# TUSB8041-Q1-4port_Hub.net
KiCad netlist of a schematic drawn in Altium Designer
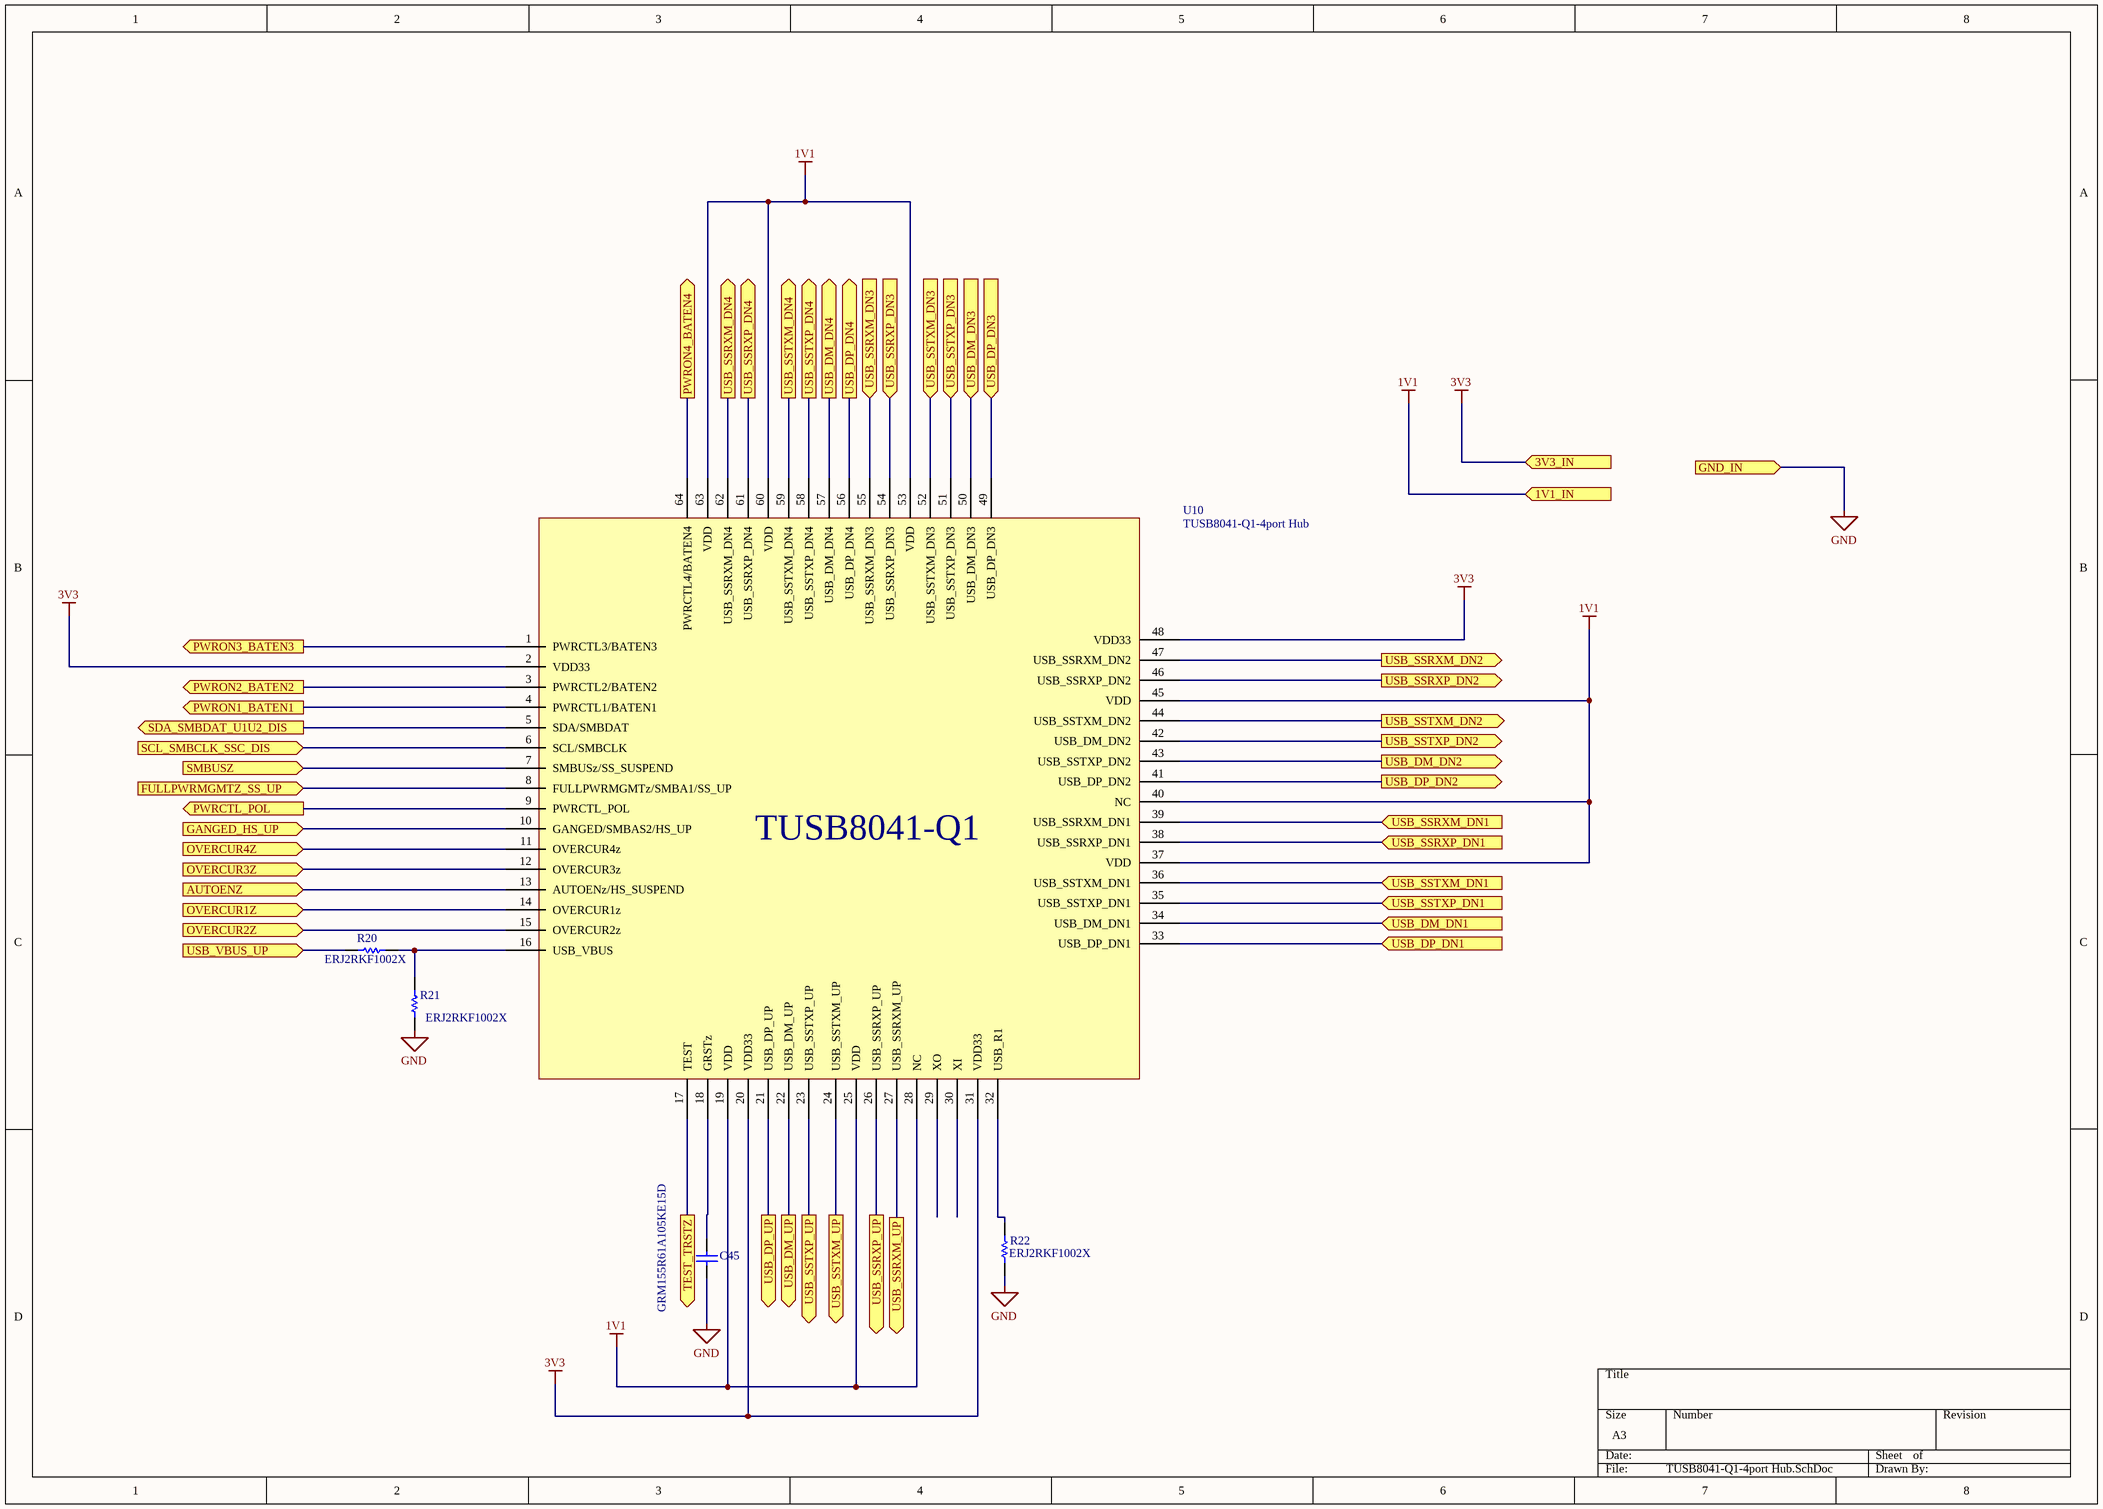
[diagram p0: TUSB8041-Q1-4port Hub.SchDoc]

(export (version "E")
  (design (tool "Eeschema 10.0.6"))
  (components
    (comp (ref "C45")
      (value "GRM155R61A105KE15D")
      (footprint "CAPC1005X55X25NL05T10")
      (fields (field (name "MANUFACTURER") "Murata"))
      (libsource (lib "Altium Content Vault") (part "CAP"))
    )
    (comp (ref "R20")
      (value "ERJ2RKF1002X")
      (footprint "RESC1005X40X25LL05T05")
      (description "Chip Resistor, 10 KOhm, +/- 1%, 0.1 W, -55 to 155 degC, 0402 (1005 Metric), RoHS, Tape and Reel")
      (fields (field (name "TOLERANCE") "1%") (field (name "MANUFACTURER") "Panasonic"))
      (libsource (lib "Altium Content Vault") (part "RES-2"))
    )
    (comp (ref "R21")
      (value "ERJ2RKF1002X")
      (footprint "RESC1005X40X25LL05T05")
      (description "Chip Resistor, 10 KOhm, +/- 1%, 0.1 W, -55 to 155 degC, 0402 (1005 Metric), RoHS, Tape and Reel")
      (fields (field (name "TOLERANCE") "1%") (field (name "MANUFACTURER") "Panasonic"))
      (libsource (lib "Altium Content Vault") (part "RES-2"))
    )
    (comp (ref "R22")
      (value "ERJ2RKF1002X")
      (footprint "RESC1005X40X25LL05T05")
      (description "Chip Resistor, 10 KOhm, +/- 1%, 0.1 W, -55 to 155 degC, 0402 (1005 Metric), RoHS, Tape and Reel")
      (fields (field (name "TOLERANCE") "1%") (field (name "MANUFACTURER") "Panasonic"))
      (libsource (lib "Altium Content Vault") (part "RES-2"))
    )
    (comp (ref "U10")
      (value "TUSB8041-Q1-4port Hub")
      (footprint "TSQFP50P1200X1200X120-64N")
      (libsource (lib "PlumPot_Library") (part "TUSB8041-Q1-4port Hub"))
    )
  )
  (nets
    (net (code "1") (name "/AUTOENZ") (class "Default")
      (node (ref "U10") (pin "13") (pinfunction "AUTOENz/HS_SUSPEND_13") (pintype "passive"))
    )
    (net (code "2") (name "/FULLPWRMGMTZ_SS_UP") (class "Default")
      (node (ref "U10") (pin "8") (pinfunction "FULLPWRMGMTz/SMBA1/SS_UP_8") (pintype "passive"))
    )
    (net (code "3") (name "/GANGED_HS_UP") (class "Default")
      (node (ref "U10") (pin "10") (pinfunction "GANGED/SMBAS2/HS_UP_10") (pintype "passive"))
    )
    (net (code "4") (name "/OVERCUR1Z") (class "Default")
      (node (ref "U10") (pin "14") (pinfunction "OVERCUR1z_14") (pintype "passive"))
    )
    (net (code "5") (name "/OVERCUR2Z") (class "Default")
      (node (ref "U10") (pin "15") (pinfunction "OVERCUR2z_15") (pintype "passive"))
    )
    (net (code "6") (name "/OVERCUR3Z") (class "Default")
      (node (ref "U10") (pin "12") (pinfunction "OVERCUR3z_12") (pintype "passive"))
    )
    (net (code "7") (name "/OVERCUR4Z") (class "Default")
      (node (ref "U10") (pin "11") (pinfunction "OVERCUR4z_11") (pintype "passive"))
    )
    (net (code "8") (name "/PWRCTL_POL") (class "Default")
      (node (ref "U10") (pin "9") (pinfunction "PWRCTL_POL_9") (pintype "passive"))
    )
    (net (code "9") (name "/PWRON1_BATEN1") (class "Default")
      (node (ref "U10") (pin "4") (pinfunction "PWRCTL1/BATEN1_4") (pintype "passive"))
    )
    (net (code "10") (name "/PWRON2_BATEN2") (class "Default")
      (node (ref "U10") (pin "3") (pinfunction "PWRCTL2/BATEN2_3") (pintype "passive"))
    )
    (net (code "11") (name "/PWRON3_BATEN3") (class "Default")
      (node (ref "U10") (pin "1") (pinfunction "PWRCTL3/BATEN3_1") (pintype "passive"))
    )
    (net (code "12") (name "/PWRON4_BATEN4") (class "Default")
      (node (ref "U10") (pin "64") (pinfunction "PWRCTL4/BATEN4_64") (pintype "passive"))
    )
    (net (code "13") (name "/SCL_SMBCLK_SSC_DIS") (class "Default")
      (node (ref "U10") (pin "6") (pinfunction "SCL/SMBCLK_6") (pintype "passive"))
    )
    (net (code "14") (name "/SDA_SMBDAT_U1U2_DIS") (class "Default")
      (node (ref "U10") (pin "5") (pinfunction "SDA/SMBDAT_5") (pintype "passive"))
    )
    (net (code "15") (name "/SMBUSZ") (class "Default")
      (node (ref "U10") (pin "7") (pinfunction "SMBUSz/SS_SUSPEND_7") (pintype "passive"))
    )
    (net (code "16") (name "/TEST_TRSTZ") (class "Default")
      (node (ref "U10") (pin "17") (pinfunction "TEST_17") (pintype "passive"))
    )
    (net (code "17") (name "/USB_DM_DN1") (class "Default")
      (node (ref "U10") (pin "34") (pinfunction "USB_DM_DN1_34") (pintype "passive"))
    )
    (net (code "18") (name "/USB_DM_DN2") (class "Default")
      (node (ref "U10") (pin "43") (pinfunction "USB_SSTXP_DN2_43") (pintype "passive"))
    )
    (net (code "19") (name "/USB_DM_DN3") (class "Default")
      (node (ref "U10") (pin "50") (pinfunction "USB_DM_DN3_50") (pintype "passive"))
    )
    (net (code "20") (name "/USB_DM_DN4") (class "Default")
      (node (ref "U10") (pin "57") (pinfunction "USB_DM_DN4_57") (pintype "passive"))
    )
    (net (code "21") (name "/USB_DM_UP") (class "Default")
      (node (ref "U10") (pin "22") (pinfunction "USB_DM_UP_22") (pintype "passive"))
    )
    (net (code "22") (name "/USB_DP_DN1") (class "Default")
      (node (ref "U10") (pin "33") (pinfunction "USB_DP_DN1_33") (pintype "passive"))
    )
    (net (code "23") (name "/USB_DP_DN2") (class "Default")
      (node (ref "U10") (pin "41") (pinfunction "USB_DP_DN2_41") (pintype "passive"))
    )
    (net (code "24") (name "/USB_DP_DN3") (class "Default")
      (node (ref "U10") (pin "49") (pinfunction "USB_DP_DN3_49") (pintype "passive"))
    )
    (net (code "25") (name "/USB_DP_DN4") (class "Default")
      (node (ref "U10") (pin "56") (pinfunction "USB_DP_DN4_56") (pintype "passive"))
    )
    (net (code "26") (name "/USB_DP_UP") (class "Default")
      (node (ref "U10") (pin "21") (pinfunction "USB_DP_UP_21") (pintype "passive"))
    )
    (net (code "27") (name "/USB_SSRXM_DN1") (class "Default")
      (node (ref "U10") (pin "39") (pinfunction "USB_SSRXM_DN1_39") (pintype "passive"))
    )
    (net (code "28") (name "/USB_SSRXM_DN2") (class "Default")
      (node (ref "U10") (pin "47") (pinfunction "USB_SSRXM_DN2_47") (pintype "passive"))
    )
    (net (code "29") (name "/USB_SSRXM_DN3") (class "Default")
      (node (ref "U10") (pin "55") (pinfunction "USB_SSRXM_DN3_55") (pintype "passive"))
    )
    (net (code "30") (name "/USB_SSRXM_DN4") (class "Default")
      (node (ref "U10") (pin "62") (pinfunction "USB_SSRXM_DN4_62") (pintype "passive"))
    )
    (net (code "31") (name "/USB_SSRXM_UP") (class "Default")
      (node (ref "U10") (pin "27") (pinfunction "USB_SSRXM_UP_27") (pintype "passive"))
    )
    (net (code "32") (name "/USB_SSRXP_DN1") (class "Default")
      (node (ref "U10") (pin "38") (pinfunction "USB_SSRXP_DN1_38") (pintype "passive"))
    )
    (net (code "33") (name "/USB_SSRXP_DN2") (class "Default")
      (node (ref "U10") (pin "46") (pinfunction "USB_SSRXP_DN2_46") (pintype "passive"))
    )
    (net (code "34") (name "/USB_SSRXP_DN3") (class "Default")
      (node (ref "U10") (pin "54") (pinfunction "USB_SSRXP_DN3_54") (pintype "passive"))
    )
    (net (code "35") (name "/USB_SSRXP_DN4") (class "Default")
      (node (ref "U10") (pin "61") (pinfunction "USB_SSRXP_DN4_61") (pintype "passive"))
    )
    (net (code "36") (name "/USB_SSRXP_UP") (class "Default")
      (node (ref "U10") (pin "26") (pinfunction "USB_SSRXP_UP_26") (pintype "passive"))
    )
    (net (code "37") (name "/USB_SSTXM_DN1") (class "Default")
      (node (ref "U10") (pin "36") (pinfunction "USB_SSTXM_DN1_36") (pintype "passive"))
    )
    (net (code "38") (name "/USB_SSTXM_DN2") (class "Default")
      (node (ref "U10") (pin "44") (pinfunction "USB_SSTXM_DN2_44") (pintype "passive"))
    )
    (net (code "39") (name "/USB_SSTXM_DN3") (class "Default")
      (node (ref "U10") (pin "52") (pinfunction "USB_SSTXM_DN3_52") (pintype "passive"))
    )
    (net (code "40") (name "/USB_SSTXM_DN4") (class "Default")
      (node (ref "U10") (pin "59") (pinfunction "USB_SSTXM_DN4_59") (pintype "passive"))
    )
    (net (code "41") (name "/USB_SSTXM_UP") (class "Default")
      (node (ref "U10") (pin "24") (pinfunction "USB_SSTXM_UP_24") (pintype "passive"))
    )
    (net (code "42") (name "/USB_SSTXP_DN1") (class "Default")
      (node (ref "U10") (pin "35") (pinfunction "USB_SSTXP_DN1_35") (pintype "passive"))
    )
    (net (code "43") (name "/USB_SSTXP_DN2") (class "Default")
      (node (ref "U10") (pin "42") (pinfunction "USB_DM_DN2_42") (pintype "passive"))
    )
    (net (code "44") (name "/USB_SSTXP_DN3") (class "Default")
      (node (ref "U10") (pin "51") (pinfunction "USB_SSTXP_DN3_51") (pintype "passive"))
    )
    (net (code "45") (name "/USB_SSTXP_DN4") (class "Default")
      (node (ref "U10") (pin "58") (pinfunction "USB_SSTXP_DN4_58") (pintype "passive"))
    )
    (net (code "46") (name "/USB_SSTXP_UP") (class "Default")
      (node (ref "U10") (pin "23") (pinfunction "USB_SSTXP_UP_23") (pintype "passive"))
    )
    (net (code "47") (name "/USB_VBUS_UP") (class "Default")
      (node (ref "R20") (pin "2") (pinfunction "2_2") (pintype "passive"))
    )
    (net (code "48") (name "1V1") (class "Default")
      (node (ref "U10") (pin "19") (pinfunction "VDD_19") (pintype "passive"))
      (node (ref "U10") (pin "25") (pinfunction "VDD_25") (pintype "passive"))
      (node (ref "U10") (pin "28") (pinfunction "NC_28") (pintype "passive"))
      (node (ref "U10") (pin "37") (pinfunction "VDD_37") (pintype "passive"))
      (node (ref "U10") (pin "40") (pinfunction "NC_40") (pintype "passive"))
      (node (ref "U10") (pin "45") (pinfunction "VDD_45") (pintype "passive"))
      (node (ref "U10") (pin "53") (pinfunction "VDD_53") (pintype "passive"))
      (node (ref "U10") (pin "60") (pinfunction "VDD_60") (pintype "passive"))
      (node (ref "U10") (pin "63") (pinfunction "VDD_63") (pintype "passive"))
    )
    (net (code "49") (name "3V3") (class "Default")
      (node (ref "U10") (pin "2") (pinfunction "VDD33_2") (pintype "passive"))
      (node (ref "U10") (pin "20") (pinfunction "VDD33_20") (pintype "passive"))
      (node (ref "U10") (pin "31") (pinfunction "VDD33_31") (pintype "passive"))
      (node (ref "U10") (pin "48") (pinfunction "VDD33_48") (pintype "passive"))
    )
    (net (code "50") (name "GND") (class "Default")
      (node (ref "C45") (pin "1") (pinfunction "1_1") (pintype "passive"))
      (node (ref "R21") (pin "1") (pinfunction "1_1") (pintype "passive"))
      (node (ref "R22") (pin "1") (pinfunction "1_1") (pintype "passive"))
    )
    (net (code "51") (name "Net-(U10-GRSTz)") (class "Default")
      (node (ref "C45") (pin "2") (pinfunction "2_2") (pintype "passive"))
      (node (ref "U10") (pin "18") (pinfunction "GRSTz_18") (pintype "passive"))
    )
    (net (code "52") (name "Net-(U10-USB_R1)") (class "Default")
      (node (ref "R22") (pin "2") (pinfunction "2_2") (pintype "passive"))
      (node (ref "U10") (pin "32") (pinfunction "USB_R1_32") (pintype "passive"))
    )
    (net (code "53") (name "Net-(U10-USB_VBUS)") (class "Default")
      (node (ref "R20") (pin "1") (pinfunction "1_1") (pintype "passive"))
      (node (ref "R21") (pin "2") (pinfunction "2_2") (pintype "passive"))
      (node (ref "U10") (pin "16") (pinfunction "USB_VBUS_16") (pintype "passive"))
    )
    (net (code "54") (name "unconnected-(U10-XI-Pad30)") (class "Default")
      (node (ref "U10") (pin "30") (pinfunction "XI_30") (pintype "passive"))
    )
    (net (code "55") (name "unconnected-(U10-XO-Pad29)") (class "Default")
      (node (ref "U10") (pin "29") (pinfunction "XO_29") (pintype "passive"))
    )
  )
)
